# WL-ADC.net
KiCad netlist of a schematic drawn in Altium Designer
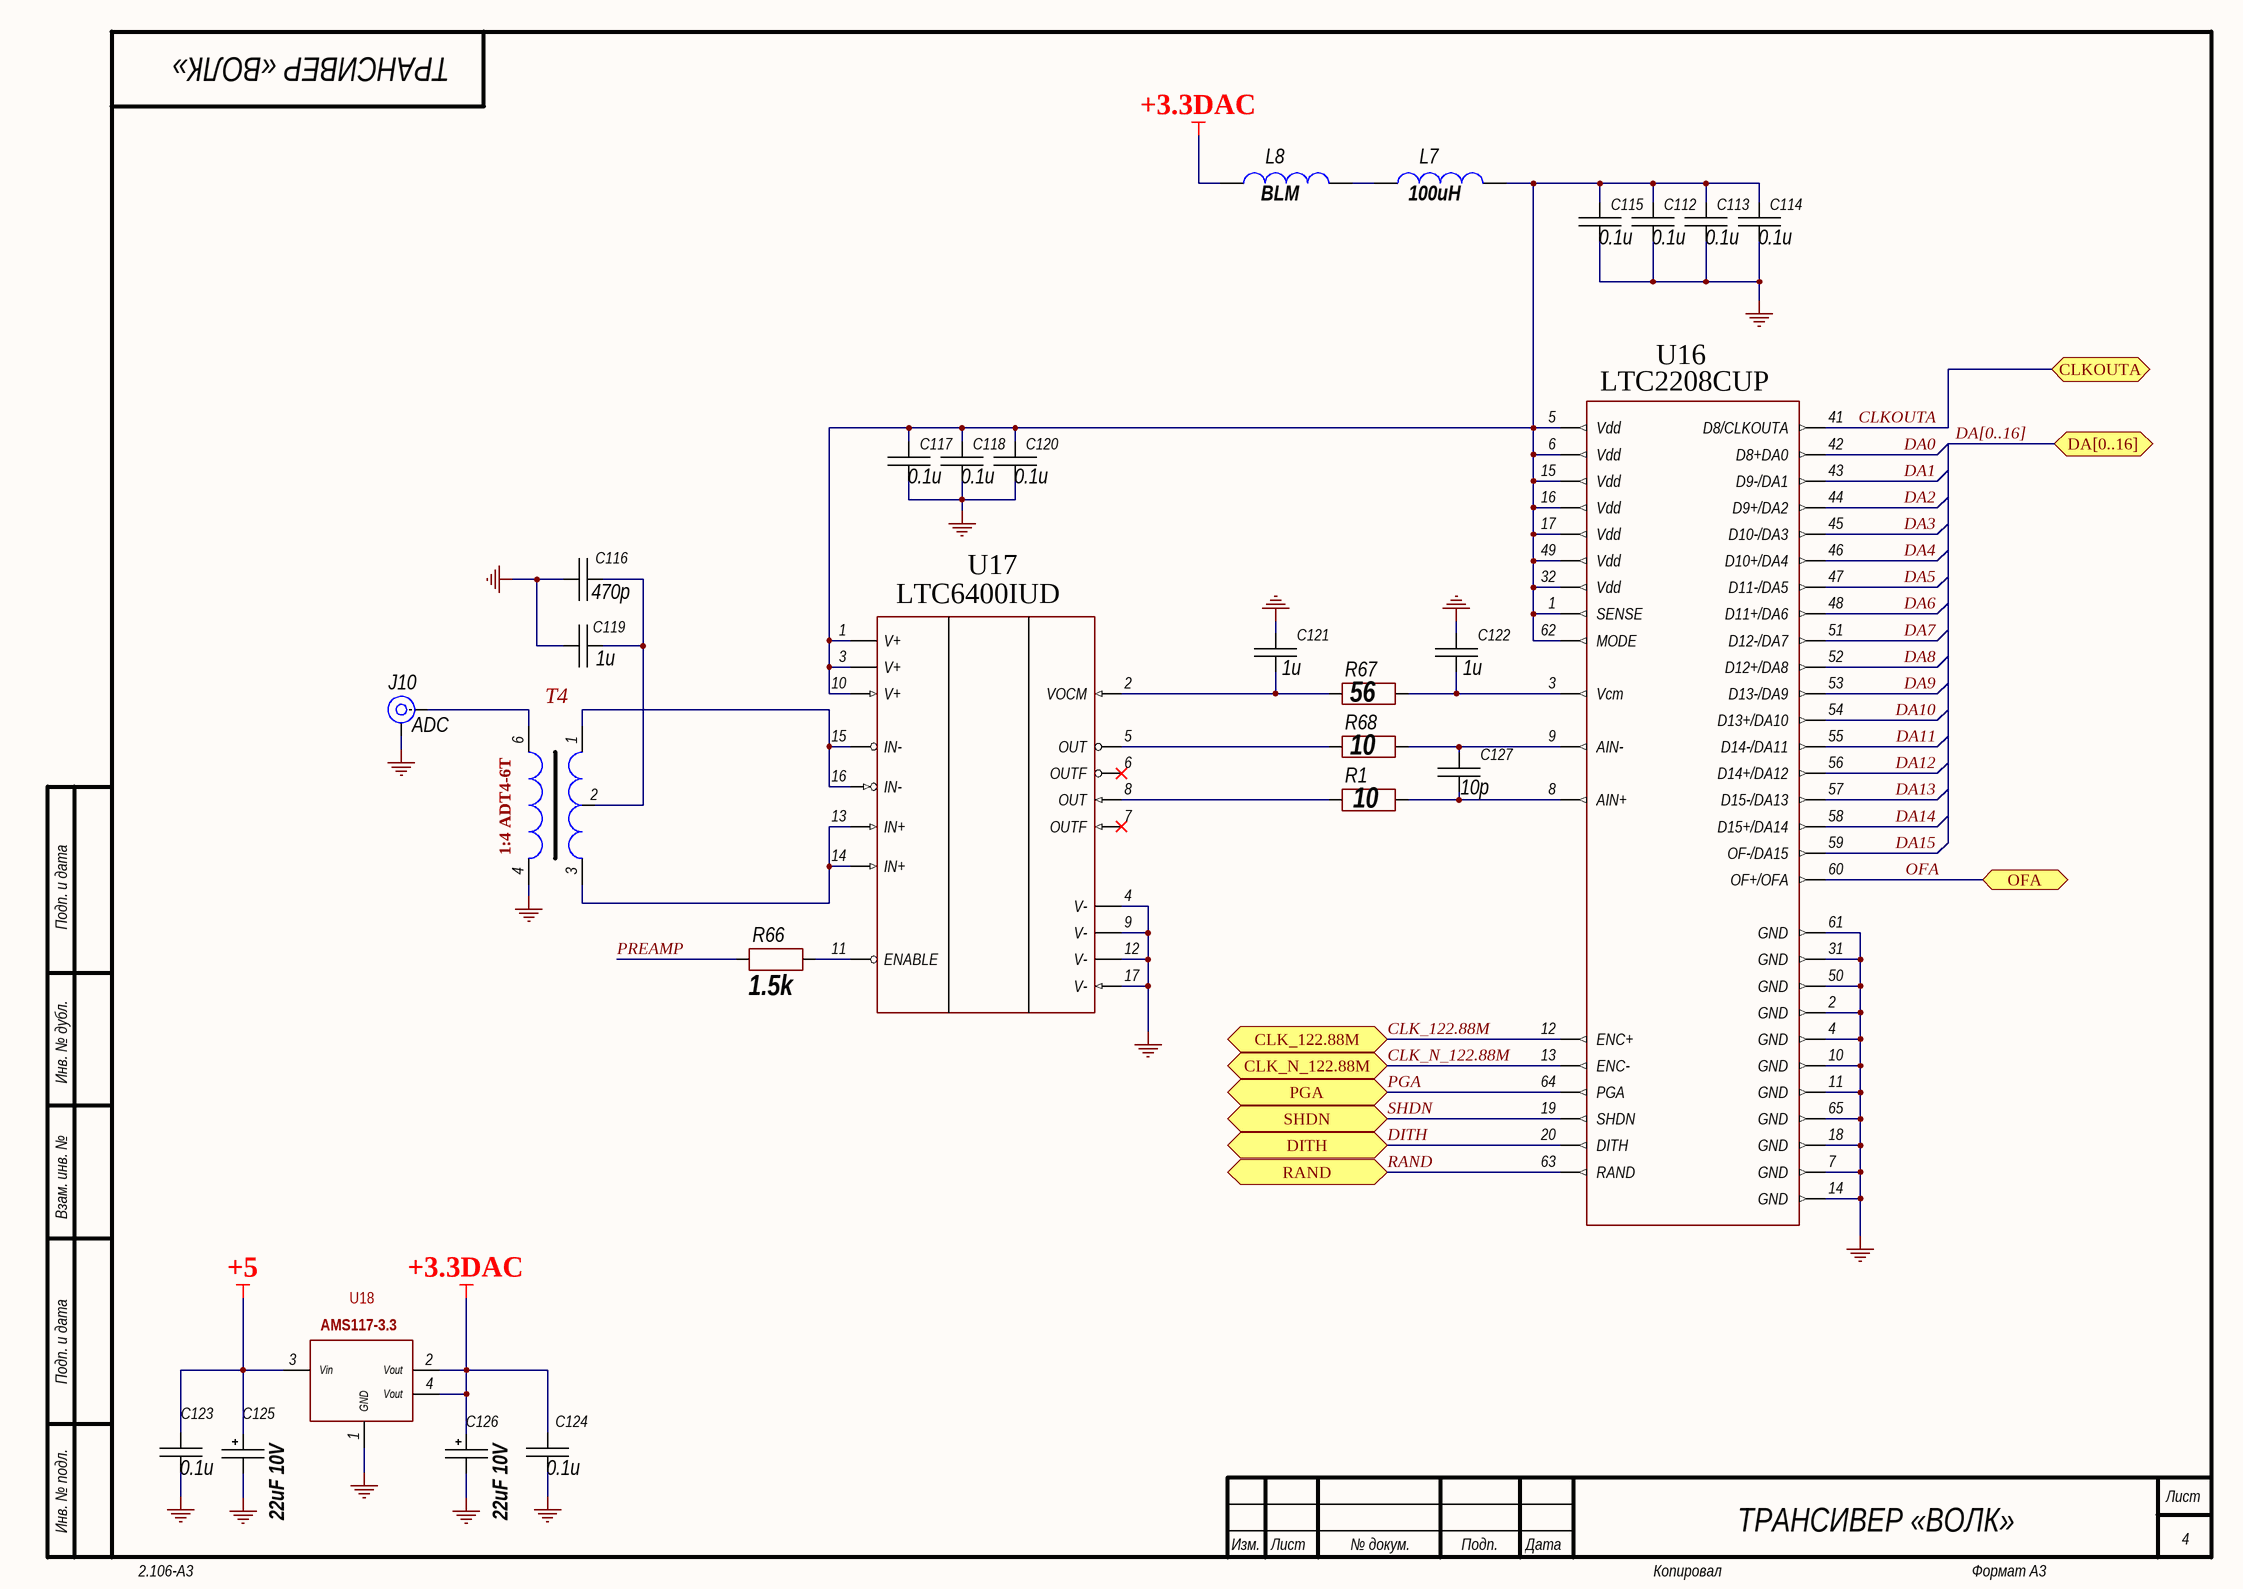
[diagram p0: WL-ADC.SchDoc]

(export (version "E")
  (design (tool "Eeschema 10.0.6"))
  (components
    (comp (ref "C112")
      (value "0.1u")
      (footprint "standard:CH0805C")
      (libsource (lib "Discrete") (part "Capacitor"))
    )
    (comp (ref "C113")
      (value "0.1u")
      (footprint "standard:CH0805C")
      (libsource (lib "Discrete") (part "Capacitor"))
    )
    (comp (ref "C114")
      (value "0.1u")
      (footprint "standard:CH0805C")
      (libsource (lib "Discrete") (part "Capacitor"))
    )
    (comp (ref "C115")
      (value "0.1u")
      (footprint "standard:CH0805C")
      (libsource (lib "Discrete") (part "Capacitor"))
    )
    (comp (ref "C116")
      (value "470p")
      (footprint "standard:CH0805C")
      (libsource (lib "Discrete") (part "Capacitor"))
    )
    (comp (ref "C117")
      (value "0.1u")
      (footprint "standard:CH0805C")
      (libsource (lib "Discrete") (part "Capacitor"))
    )
    (comp (ref "C118")
      (value "0.1u")
      (footprint "standard:CH0805C")
      (libsource (lib "Discrete") (part "Capacitor"))
    )
    (comp (ref "C119")
      (value "1u")
      (footprint "standard:CH0805C")
      (libsource (lib "Discrete") (part "Capacitor"))
    )
    (comp (ref "C120")
      (value "0.1u")
      (footprint "standard:CH0805C")
      (libsource (lib "Discrete") (part "Capacitor"))
    )
    (comp (ref "C121")
      (value "1u")
      (footprint "standard:CH0805C")
      (libsource (lib "Discrete") (part "Capacitor"))
    )
    (comp (ref "C122")
      (value "1u")
      (footprint "standard:CH0805C")
      (libsource (lib "Discrete") (part "Capacitor"))
    )
    (comp (ref "C123")
      (value "0.1u")
      (footprint "standard:CH0805C")
      (libsource (lib "Discrete") (part "Capacitor"))
    )
    (comp (ref "C124")
      (value "0.1u")
      (footprint "standard:CH0805C")
      (libsource (lib "Discrete") (part "Capacitor"))
    )
    (comp (ref "C125")
      (value "22uF 10V")
      (footprint "standard:TANTAL_B")
      (libsource (lib "Discrete") (part "TantalCap"))
    )
    (comp (ref "C126")
      (value "22uF 10V")
      (footprint "standard:TANTAL_B")
      (libsource (lib "Discrete") (part "TantalCap"))
    )
    (comp (ref "C127")
      (value "10p")
      (footprint "standard:CH0805C")
      (libsource (lib "Discrete") (part "Capacitor"))
    )
    (comp (ref "J10")
      (value "ADC")
      (footprint "custom:CON: SMA")
      (description "RF")
      (libsource (lib "Connectors") (part "SMA"))
    )
    (comp (ref "L7") (value "100uH") (footprint "L1210") (libsource (lib "Discrete") (part "Inductor")))
    (comp (ref "L8")
      (value "BLM")
      (footprint "standard:CH0805L")
      (libsource (lib "Discrete") (part "Inductor"))
    )
    (comp (ref "R1")
      (value "10")
      (footprint "standard:CH0805R")
      (libsource (lib "Discrete") (part "Resistor"))
    )
    (comp (ref "R66")
      (value "1.5k")
      (footprint "standard:CH0805R")
      (libsource (lib "Discrete") (part "Resistor"))
    )
    (comp (ref "R67")
      (value "56")
      (footprint "standard:CH0805R")
      (libsource (lib "Discrete") (part "Resistor"))
    )
    (comp (ref "R68")
      (value "10")
      (footprint "standard:CH0805R")
      (libsource (lib "Discrete") (part "Resistor"))
    )
    (comp (ref "T4")
      (value "1:4 ADT4-6T")
      (footprint "TC1-4")
      (libsource (lib "Transformers") (part "TC4-1"))
    )
    (comp (ref "U16")
      (value "LTC2208CUP")
      (footprint "64-QFN (9x9)")
      (libsource (lib "Digital") (part "LTC2208CUP"))
    )
    (comp (ref "U17")
      (value "LTC6400IUD")
      (footprint "16-QFN 3x3")
      (libsource (lib "Digital") (part "LTC6400IUD"))
    )
    (comp (ref "U18") (value "AMS117-3.3") (footprint "SOT223") (libsource (lib "Analog") (part "AMS117")))
  )
  (nets
    (net (code "2") (name "+3.3DAC") (class "Default")
      (node (ref "C124") (pin "2") (pinfunction "2_2") (pintype "power_in"))
      (node (ref "C126") (pin "1") (pinfunction "1_1") (pintype "power_in"))
      (node (ref "L8") (pin "2") (pinfunction "2_2") (pintype "passive"))
      (node (ref "U18") (pin "2") (pinfunction "Vout_2") (pintype "passive"))
      (node (ref "U18") (pin "4") (pinfunction "Vout_4") (pintype "passive"))
    )
    (net (code "3") (name "+5") (class "Default")
      (node (ref "C123") (pin "2") (pinfunction "2_2") (pintype "power_in"))
      (node (ref "C125") (pin "1") (pinfunction "1_1") (pintype "power_in"))
      (node (ref "U18") (pin "3") (pinfunction "Vin_3") (pintype "passive"))
    )
    (net (code "4") (name "/CLKOUTA") (class "Default")
      (node (ref "U16") (pin "41") (pinfunction "D8/CLKOUTA_41") (pintype "output"))
    )
    (net (code "5") (name "/CLK_122.88M") (class "Default")
      (node (ref "U16") (pin "12") (pinfunction "ENC+_12") (pintype "output"))
    )
    (net (code "6") (name "/CLK_N_122.88M") (class "Default")
      (node (ref "U16") (pin "13") (pinfunction "ENC-_13") (pintype "output"))
    )
    (net (code "7") (name "/DA0") (class "Default")
      (node (ref "U16") (pin "42") (pinfunction "D8+DA0_42") (pintype "output"))
    )
    (net (code "8") (name "/DA1") (class "Default")
      (node (ref "U16") (pin "43") (pinfunction "D9-/DA1_43") (pintype "output"))
    )
    (net (code "9") (name "/DA2") (class "Default")
      (node (ref "U16") (pin "44") (pinfunction "D9+/DA2_44") (pintype "output"))
    )
    (net (code "10") (name "/DA3") (class "Default")
      (node (ref "U16") (pin "45") (pinfunction "D10-/DA3_45") (pintype "output"))
    )
    (net (code "11") (name "/DA4") (class "Default")
      (node (ref "U16") (pin "46") (pinfunction "D10+/DA4_46") (pintype "output"))
    )
    (net (code "12") (name "/DA5") (class "Default")
      (node (ref "U16") (pin "47") (pinfunction "D11-/DA5_47") (pintype "output"))
    )
    (net (code "13") (name "/DA6") (class "Default")
      (node (ref "U16") (pin "48") (pinfunction "D11+/DA6_48") (pintype "output"))
    )
    (net (code "14") (name "/DA7") (class "Default")
      (node (ref "U16") (pin "51") (pinfunction "D12-/DA7_51") (pintype "output"))
    )
    (net (code "15") (name "/DA8") (class "Default")
      (node (ref "U16") (pin "52") (pinfunction "D12+/DA8_52") (pintype "output"))
    )
    (net (code "16") (name "/DA9") (class "Default")
      (node (ref "U16") (pin "53") (pinfunction "D13-/DA9_53") (pintype "output"))
    )
    (net (code "17") (name "/DA10") (class "Default")
      (node (ref "U16") (pin "54") (pinfunction "D13+/DA10_54") (pintype "output"))
    )
    (net (code "18") (name "/DA11") (class "Default")
      (node (ref "U16") (pin "55") (pinfunction "D14-/DA11_55") (pintype "output"))
    )
    (net (code "19") (name "/DA12") (class "Default")
      (node (ref "U16") (pin "56") (pinfunction "D14+/DA12_56") (pintype "output"))
    )
    (net (code "20") (name "/DA13") (class "Default")
      (node (ref "U16") (pin "57") (pinfunction "D15-/DA13_57") (pintype "output"))
    )
    (net (code "21") (name "/DA14") (class "Default")
      (node (ref "U16") (pin "58") (pinfunction "D15+/DA14_58") (pintype "output"))
    )
    (net (code "22") (name "/DA15") (class "Default")
      (node (ref "U16") (pin "59") (pinfunction "OF-/DA15_59") (pintype "output"))
    )
    (net (code "24") (name "/DITH") (class "Default")
      (node (ref "U16") (pin "20") (pinfunction "DITH_20") (pintype "output"))
    )
    (net (code "25") (name "/OFA") (class "Default")
      (node (ref "U16") (pin "60") (pinfunction "OF+/OFA_60") (pintype "output"))
    )
    (net (code "26") (name "/PGA") (class "Default")
      (node (ref "U16") (pin "64") (pinfunction "PGA_64") (pintype "output"))
    )
    (net (code "27") (name "/PREAMP") (class "Default")
      (node (ref "R66") (pin "2") (pinfunction "2_2") (pintype "passive"))
    )
    (net (code "28") (name "/RAND") (class "Default")
      (node (ref "U16") (pin "63") (pinfunction "RAND_63") (pintype "output"))
    )
    (net (code "29") (name "/SHDN") (class "Default")
      (node (ref "U16") (pin "19") (pinfunction "SHDN_19") (pintype "output"))
    )
    (net (code "30") (name "GND") (class "Default")
      (node (ref "C112") (pin "1") (pinfunction "1_1") (pintype "power_in"))
      (node (ref "C113") (pin "1") (pinfunction "1_1") (pintype "power_in"))
      (node (ref "C114") (pin "1") (pinfunction "1_1") (pintype "power_in"))
      (node (ref "C115") (pin "1") (pinfunction "1_1") (pintype "power_in"))
      (node (ref "C116") (pin "2") (pinfunction "2_2") (pintype "power_in"))
      (node (ref "C117") (pin "1") (pinfunction "1_1") (pintype "power_in"))
      (node (ref "C118") (pin "1") (pinfunction "1_1") (pintype "power_in"))
      (node (ref "C119") (pin "2") (pinfunction "2_2") (pintype "power_in"))
      (node (ref "C120") (pin "1") (pinfunction "1_1") (pintype "power_in"))
      (node (ref "C121") (pin "2") (pinfunction "2_2") (pintype "power_in"))
      (node (ref "C122") (pin "2") (pinfunction "2_2") (pintype "power_in"))
      (node (ref "C123") (pin "1") (pinfunction "1_1") (pintype "power_in"))
      (node (ref "C124") (pin "1") (pinfunction "1_1") (pintype "power_in"))
      (node (ref "C125") (pin "2") (pinfunction "2_2") (pintype "power_in"))
      (node (ref "C126") (pin "2") (pinfunction "2_2") (pintype "power_in"))
      (node (ref "J10") (pin "2") (pinfunction "IN_2") (pintype "passive"))
      (node (ref "T4") (pin "4") (pinfunction "4_4") (pintype "power_in"))
      (node (ref "U16") (pin "10") (pinfunction "GND_10") (pintype "output"))
      (node (ref "U16") (pin "11") (pinfunction "GND_11") (pintype "output"))
      (node (ref "U16") (pin "14") (pinfunction "GND_14") (pintype "output"))
      (node (ref "U16") (pin "18") (pinfunction "GND_18") (pintype "output"))
      (node (ref "U16") (pin "2") (pinfunction "GND_2") (pintype "output"))
      (node (ref "U16") (pin "31") (pinfunction "GND_31") (pintype "output"))
      (node (ref "U16") (pin "4") (pinfunction "GND_4") (pintype "output"))
      (node (ref "U16") (pin "50") (pinfunction "GND_50") (pintype "output"))
      (node (ref "U16") (pin "61") (pinfunction "GND_61") (pintype "output"))
      (node (ref "U16") (pin "65") (pinfunction "GND_65") (pintype "output"))
      (node (ref "U16") (pin "7") (pinfunction "GND_7") (pintype "output"))
      (node (ref "U17") (pin "12") (pinfunction "V-_12") (pintype "power_in"))
      (node (ref "U17") (pin "17") (pinfunction "V-_17") (pintype "input"))
      (node (ref "U17") (pin "4") (pinfunction "V-_4") (pintype "passive"))
      (node (ref "U17") (pin "9") (pinfunction "V-_9") (pintype "power_in"))
      (node (ref "U18") (pin "1") (pinfunction "GND_1") (pintype "passive"))
    )
    (net (code "31") (name "Net-(C116-Pad1)") (class "Default")
      (node (ref "C116") (pin "1") (pinfunction "1_1") (pintype "power_in"))
      (node (ref "C119") (pin "1") (pinfunction "1_1") (pintype "power_in"))
      (node (ref "T4") (pin "2") (pinfunction "2_2") (pintype "power_in"))
    )
    (net (code "32") (name "Net-(J10-IN-Pad1)") (class "Default")
      (node (ref "J10") (pin "1") (pinfunction "IN_1") (pintype "passive"))
      (node (ref "T4") (pin "6") (pinfunction "6_6") (pintype "power_in"))
    )
    (net (code "33") (name "Net-(L7-Pad2)") (class "Default")
      (node (ref "L7") (pin "2") (pinfunction "2_2") (pintype "passive"))
      (node (ref "L8") (pin "1") (pinfunction "1_1") (pintype "passive"))
    )
    (net (code "34") (name "Net-(R1-Pad2)") (class "Default")
      (node (ref "R1") (pin "2") (pinfunction "2_2") (pintype "passive"))
      (node (ref "U17") (pin "8") (pinfunction "OUT_8") (pintype "input"))
    )
    (net (code "35") (name "Net-(R68-Pad2)") (class "Default")
      (node (ref "R68") (pin "2") (pinfunction "2_2") (pintype "passive"))
      (node (ref "U17") (pin "5") (pinfunction "OUT_5") (pintype "passive"))
    )
    (net (code "36") (name "Net-(T4-Pad1)") (class "Default")
      (node (ref "T4") (pin "1") (pinfunction "1_1") (pintype "power_in"))
      (node (ref "U17") (pin "15") (pinfunction "IN-_15") (pintype "passive"))
      (node (ref "U17") (pin "16") (pinfunction "IN-_16") (pintype "input"))
    )
    (net (code "37") (name "Net-(T4-Pad3)") (class "Default")
      (node (ref "T4") (pin "3") (pinfunction "3_3") (pintype "power_in"))
      (node (ref "U17") (pin "13") (pinfunction "IN+_13") (pintype "input"))
      (node (ref "U17") (pin "14") (pinfunction "IN+_14") (pintype "input"))
    )
    (net (code "38") (name "Net-(U16-AIN+)") (class "Default")
      (node (ref "C127") (pin "1") (pinfunction "1_1") (pintype "power_in"))
      (node (ref "R1") (pin "1") (pinfunction "1_1") (pintype "passive"))
      (node (ref "U16") (pin "8") (pinfunction "AIN+_8") (pintype "output"))
    )
    (net (code "39") (name "Net-(U16-AIN-)") (class "Default")
      (node (ref "C127") (pin "2") (pinfunction "2_2") (pintype "power_in"))
      (node (ref "R68") (pin "1") (pinfunction "1_1") (pintype "passive"))
      (node (ref "U16") (pin "9") (pinfunction "AIN-_9") (pintype "output"))
    )
    (net (code "40") (name "Net-(U16-MODE)") (class "Default")
      (node (ref "C112") (pin "2") (pinfunction "2_2") (pintype "power_in"))
      (node (ref "C113") (pin "2") (pinfunction "2_2") (pintype "power_in"))
      (node (ref "C114") (pin "2") (pinfunction "2_2") (pintype "power_in"))
      (node (ref "C115") (pin "2") (pinfunction "2_2") (pintype "power_in"))
      (node (ref "C117") (pin "2") (pinfunction "2_2") (pintype "power_in"))
      (node (ref "C118") (pin "2") (pinfunction "2_2") (pintype "power_in"))
      (node (ref "C120") (pin "2") (pinfunction "2_2") (pintype "power_in"))
      (node (ref "L7") (pin "1") (pinfunction "1_1") (pintype "passive"))
      (node (ref "U16") (pin "1") (pinfunction "SENSE_1") (pintype "output"))
      (node (ref "U16") (pin "15") (pinfunction "Vdd_15") (pintype "output"))
      (node (ref "U16") (pin "16") (pinfunction "Vdd_16") (pintype "output"))
      (node (ref "U16") (pin "17") (pinfunction "Vdd_17") (pintype "output"))
      (node (ref "U16") (pin "32") (pinfunction "Vdd_32") (pintype "output"))
      (node (ref "U16") (pin "49") (pinfunction "Vdd_49") (pintype "output"))
      (node (ref "U16") (pin "5") (pinfunction "Vdd_5") (pintype "output"))
      (node (ref "U16") (pin "6") (pinfunction "Vdd_6") (pintype "output"))
      (node (ref "U16") (pin "62") (pinfunction "MODE_62") (pintype "output"))
      (node (ref "U17") (pin "1") (pinfunction "V+_1") (pintype "passive"))
      (node (ref "U17") (pin "10") (pinfunction "V+_10") (pintype "input"))
      (node (ref "U17") (pin "3") (pinfunction "V+_3") (pintype "power_in"))
    )
    (net (code "41") (name "Net-(U16-Vcm)") (class "Default")
      (node (ref "C122") (pin "1") (pinfunction "1_1") (pintype "power_in"))
      (node (ref "R67") (pin "1") (pinfunction "1_1") (pintype "passive"))
      (node (ref "U16") (pin "3") (pinfunction "Vcm_3") (pintype "output"))
    )
    (net (code "42") (name "Net-(U17-ENABLE)") (class "Default")
      (node (ref "R66") (pin "1") (pinfunction "1_1") (pintype "passive"))
      (node (ref "U17") (pin "11") (pinfunction "ENABLE_11") (pintype "passive"))
    )
    (net (code "43") (name "Net-(U17-VOCM)") (class "Default")
      (node (ref "C121") (pin "1") (pinfunction "1_1") (pintype "power_in"))
      (node (ref "R67") (pin "2") (pinfunction "2_2") (pintype "passive"))
      (node (ref "U17") (pin "2") (pinfunction "VOCM_2") (pintype "input"))
    )
    (net (code "44") (name "unconnected-(U17-OUTF-Pad6)") (class "Default")
      (node (ref "U17") (pin "6") (pinfunction "OUTF_6") (pintype "passive+no_connect"))
    )
    (net (code "45") (name "unconnected-(U17-OUTF-Pad7)") (class "Default")
      (node (ref "U17") (pin "7") (pinfunction "OUTF_7") (pintype "input+no_connect"))
    )
  )
)
